# Main.net
KiCad netlist of a schematic drawn in Altium Designer
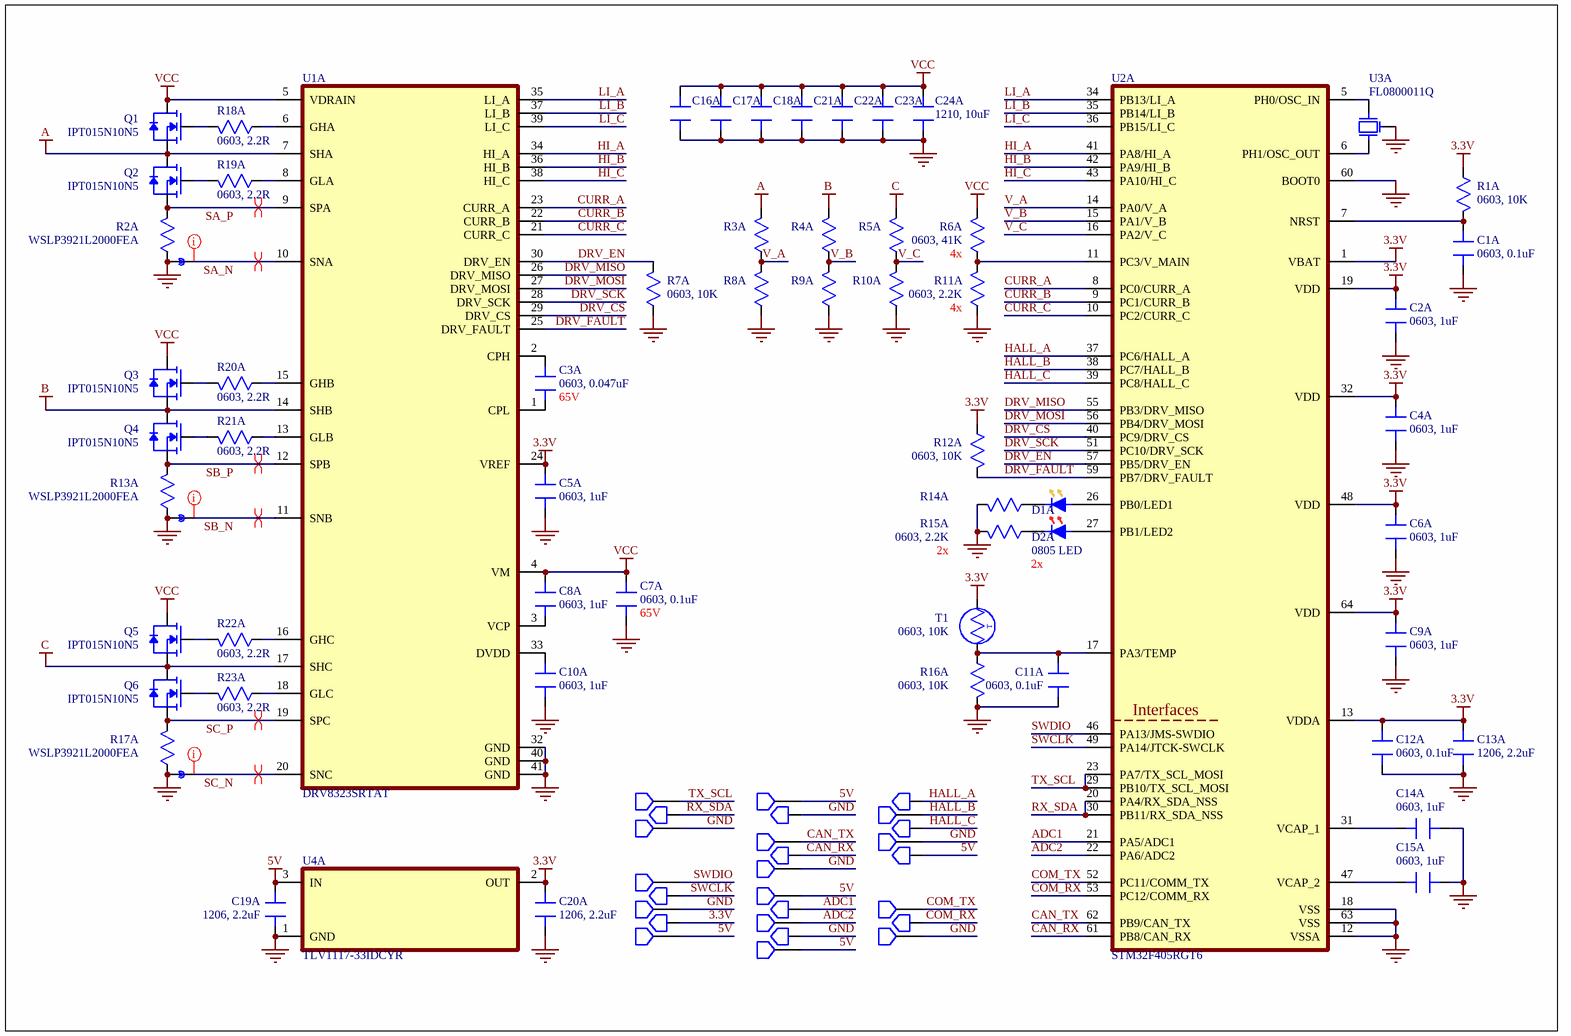
[diagram p0: Main.SchDoc]

(export (version "E")
  (design (tool "Eeschema 10.0.6"))
  (components
    (comp (ref "*1") (value "NetTie") (footprint "NETTİE") (libsource (lib "Passives") (part "NetTie")))
    (comp (ref "*2") (value "NetTie") (footprint "NETTİE") (libsource (lib "Passives") (part "NetTie")))
    (comp (ref "*3") (value "NetTie") (footprint "NETTİE") (libsource (lib "Passives") (part "NetTie")))
    (comp (ref "C1A")
      (value "0603, 0.1uF")
      (footprint "CAP 0603_1608")
      (libsource (lib "Passives") (part "0603 Kapasitör"))
    )
    (comp (ref "C2A")
      (value "0603, 1uF")
      (footprint "CAP 0603_1608")
      (libsource (lib "Passives") (part "0603 Kapasitör"))
    )
    (comp (ref "C3A")
      (value "0603, 0.047uF")
      (footprint "CAP 0603_1608")
      (libsource (lib "Passives") (part "0603 Kapasitör"))
    )
    (comp (ref "C4A")
      (value "0603, 1uF")
      (footprint "CAP 0603_1608")
      (libsource (lib "Passives") (part "0603 Kapasitör"))
    )
    (comp (ref "C5A")
      (value "0603, 1uF")
      (footprint "CAP 0603_1608")
      (libsource (lib "Passives") (part "0603 Kapasitör"))
    )
    (comp (ref "C6A")
      (value "0603, 1uF")
      (footprint "CAP 0603_1608")
      (libsource (lib "Passives") (part "0603 Kapasitör"))
    )
    (comp (ref "C7A")
      (value "0603, 0.1uF")
      (footprint "CAP 0603_1608")
      (libsource (lib "Passives") (part "0603 Kapasitör"))
    )
    (comp (ref "C8A")
      (value "0603, 1uF")
      (footprint "CAP 0603_1608")
      (libsource (lib "Passives") (part "0603 Kapasitör"))
    )
    (comp (ref "C9A")
      (value "0603, 1uF")
      (footprint "CAP 0603_1608")
      (libsource (lib "Passives") (part "0603 Kapasitör"))
    )
    (comp (ref "C10A")
      (value "0603, 1uF")
      (footprint "CAP 0603_1608")
      (libsource (lib "Passives") (part "0603 Kapasitör"))
    )
    (comp (ref "C11A")
      (value "0603, 0.1uF")
      (footprint "CAP 0603_1608")
      (libsource (lib "Passives") (part "0603 Kapasitör"))
    )
    (comp (ref "C12A")
      (value "0603, 0.1uF")
      (footprint "CAP 0603_1608")
      (libsource (lib "Passives") (part "0603 Kapasitör"))
    )
    (comp (ref "C13A")
      (value "1206, 2.2uF")
      (footprint "CAP 1206_3216")
      (libsource (lib "Passives") (part "1206 Kapasitör"))
    )
    (comp (ref "C14A")
      (value "0603, 1uF")
      (footprint "CAP 0603_1608")
      (libsource (lib "Passives") (part "0603 Kapasitör"))
    )
    (comp (ref "C15A")
      (value "0603, 1uF")
      (footprint "CAP 0603_1608")
      (libsource (lib "Passives") (part "0603 Kapasitör"))
    )
    (comp (ref "C16A")
      (value "1210, 10uF")
      (footprint "CAP 1210_3225 - 2.5MM")
      (libsource (lib "Passives") (part "1210 Kapasitör"))
    )
    (comp (ref "C17A")
      (value "1210, 10uF")
      (footprint "CAP 1210_3225 - 2.5MM")
      (libsource (lib "Passives") (part "1210 Kapasitör"))
    )
    (comp (ref "C18A")
      (value "1210, 10uF")
      (footprint "CAP 1210_3225 - 2.5MM")
      (libsource (lib "Passives") (part "1210 Kapasitör"))
    )
    (comp (ref "C19A")
      (value "1206, 2.2uF")
      (footprint "CAP 1206_3216")
      (libsource (lib "Passives") (part "1206 Kapasitör"))
    )
    (comp (ref "C20A")
      (value "1206, 2.2uF")
      (footprint "CAP 1206_3216")
      (libsource (lib "Passives") (part "1206 Kapasitör"))
    )
    (comp (ref "C21A")
      (value "1210, 10uF")
      (footprint "CAP 1210_3225 - 2.5MM")
      (libsource (lib "Passives") (part "1210 Kapasitör"))
    )
    (comp (ref "C22A")
      (value "1210, 10uF")
      (footprint "CAP 1210_3225 - 2.5MM")
      (libsource (lib "Passives") (part "1210 Kapasitör"))
    )
    (comp (ref "C23A")
      (value "1210, 10uF")
      (footprint "CAP 1210_3225 - 2.5MM")
      (libsource (lib "Passives") (part "1210 Kapasitör"))
    )
    (comp (ref "C24A")
      (value "1210, 10uF")
      (footprint "CAP 1210_3225 - 2.5MM")
      (libsource (lib "Passives") (part "1210 Kapasitör"))
    )
    (comp (ref "D1A")
      (value "0805 LED Yellow")
      (footprint "LED 0805_2012 YELLOW")
      (libsource (lib "Passives") (part "0805 LED Yellow"))
    )
    (comp (ref "D2A")
      (value "0805 LED Red")
      (footprint "LED 0805_2012 RED")
      (libsource (lib "Passives") (part "0805 LED Red"))
    )
    (comp (ref "P1") (value "Pad1") (footprint "PAD") (libsource (lib "Passives") (part "Pad1")))
    (comp (ref "P2") (value "Pad1") (footprint "PAD") (libsource (lib "Passives") (part "Pad1")))
    (comp (ref "P4") (value "Pad0") (footprint "PAD") (libsource (lib "Passives") (part "Pad0")))
    (comp (ref "P5") (value "Pad0") (footprint "PAD") (libsource (lib "Passives") (part "Pad0")))
    (comp (ref "P6") (value "Pad0") (footprint "PAD") (libsource (lib "Passives") (part "Pad0")))
    (comp (ref "P7") (value "Pad1") (footprint "PAD") (libsource (lib "Passives") (part "Pad1")))
    (comp (ref "P8") (value "Pad1") (footprint "PAD") (libsource (lib "Passives") (part "Pad1")))
    (comp (ref "P9") (value "Pad1") (footprint "PAD") (libsource (lib "Passives") (part "Pad1")))
    (comp (ref "P10") (value "Pad0") (footprint "PAD") (libsource (lib "Passives") (part "Pad0")))
    (comp (ref "P11") (value "Pad0") (footprint "PAD") (libsource (lib "Passives") (part "Pad0")))
    (comp (ref "P12") (value "Pad1") (footprint "PAD") (libsource (lib "Passives") (part "Pad1")))
    (comp (ref "P13") (value "Pad1") (footprint "PAD") (libsource (lib "Passives") (part "Pad1")))
    (comp (ref "P14") (value "Pad0") (footprint "PAD") (libsource (lib "Passives") (part "Pad0")))
    (comp (ref "P15") (value "Pad1") (footprint "PAD") (libsource (lib "Passives") (part "Pad1")))
    (comp (ref "P16") (value "Pad0") (footprint "PAD") (libsource (lib "Passives") (part "Pad0")))
    (comp (ref "P17") (value "Pad0") (footprint "PAD") (libsource (lib "Passives") (part "Pad0")))
    (comp (ref "P18") (value "Pad1") (footprint "PAD") (libsource (lib "Passives") (part "Pad1")))
    (comp (ref "P19") (value "Pad1") (footprint "PAD") (libsource (lib "Passives") (part "Pad1")))
    (comp (ref "P20") (value "Pad1") (footprint "PAD") (libsource (lib "Passives") (part "Pad1")))
    (comp (ref "P21") (value "Pad0") (footprint "PAD") (libsource (lib "Passives") (part "Pad0")))
    (comp (ref "P22") (value "Pad0") (footprint "PAD") (libsource (lib "Passives") (part "Pad0")))
    (comp (ref "P23") (value "Pad0") (footprint "PAD") (libsource (lib "Passives") (part "Pad0")))
    (comp (ref "P24") (value "Pad1") (footprint "PAD") (libsource (lib "Passives") (part "Pad1")))
    (comp (ref "P25") (value "Pad1") (footprint "PAD") (libsource (lib "Passives") (part "Pad1")))
    (comp (ref "P26") (value "Pad1") (footprint "PAD") (libsource (lib "Passives") (part "Pad1")))
    (comp (ref "P27") (value "Pad1") (footprint "PAD") (libsource (lib "Passives") (part "Pad1")))
    (comp (ref "Q1")
      (value "IPT015N10N5")
      (footprint "IPT015N10N5")
      (libsource (lib "IPT015N10N5") (part "IPT015N10N5"))
    )
    (comp (ref "Q2")
      (value "IPT015N10N5")
      (footprint "IPT015N10N5")
      (libsource (lib "IPT015N10N5") (part "IPT015N10N5"))
    )
    (comp (ref "Q3")
      (value "IPT015N10N5")
      (footprint "IPT015N10N5")
      (libsource (lib "IPT015N10N5") (part "IPT015N10N5"))
    )
    (comp (ref "Q4")
      (value "IPT015N10N5")
      (footprint "IPT015N10N5")
      (libsource (lib "IPT015N10N5") (part "IPT015N10N5"))
    )
    (comp (ref "Q5")
      (value "IPT015N10N5")
      (footprint "IPT015N10N5")
      (libsource (lib "IPT015N10N5") (part "IPT015N10N5"))
    )
    (comp (ref "Q6")
      (value "IPT015N10N5")
      (footprint "IPT015N10N5")
      (libsource (lib "IPT015N10N5") (part "IPT015N10N5"))
    )
    (comp (ref "R1A")
      (value "0603, 10K")
      (footprint "RES 0603_1608")
      (libsource (lib "Passives") (part "0603 Direnç"))
    )
    (comp (ref "R2A")
      (value "WSLP3921L2000FEA")
      (footprint "WSLP3921L2000FEA")
      (libsource (lib "WSLP3921L2000FEA") (part "WSLP3921L2000FEA"))
    )
    (comp (ref "R3A")
      (value "0603, 41K")
      (footprint "RES 0603_1608")
      (libsource (lib "Passives") (part "0603 Direnç"))
    )
    (comp (ref "R4A")
      (value "0603, 41K")
      (footprint "RES 0603_1608")
      (libsource (lib "Passives") (part "0603 Direnç"))
    )
    (comp (ref "R5A")
      (value "0603, 41K")
      (footprint "RES 0603_1608")
      (libsource (lib "Passives") (part "0603 Direnç"))
    )
    (comp (ref "R6A")
      (value "0603, 41K")
      (footprint "RES 0603_1608")
      (libsource (lib "Passives") (part "0603 Direnç"))
    )
    (comp (ref "R7A")
      (value "0603, 10K")
      (footprint "RES 0603_1608")
      (libsource (lib "Passives") (part "0603 Direnç"))
    )
    (comp (ref "R8A")
      (value "0603, 2.2K")
      (footprint "RES 0603_1608")
      (libsource (lib "Passives") (part "0603 Direnç"))
    )
    (comp (ref "R9A")
      (value "0603, 2.2K")
      (footprint "RES 0603_1608")
      (libsource (lib "Passives") (part "0603 Direnç"))
    )
    (comp (ref "R10A")
      (value "0603, 2.2K")
      (footprint "RES 0603_1608")
      (libsource (lib "Passives") (part "0603 Direnç"))
    )
    (comp (ref "R11A")
      (value "0603, 2.2K")
      (footprint "RES 0603_1608")
      (libsource (lib "Passives") (part "0603 Direnç"))
    )
    (comp (ref "R12A")
      (value "0603, 10K")
      (footprint "RES 0603_1608")
      (libsource (lib "Passives") (part "0603 Direnç"))
    )
    (comp (ref "R13A")
      (value "WSLP3921L2000FEA")
      (footprint "WSLP3921L2000FEA")
      (libsource (lib "WSLP3921L2000FEA") (part "WSLP3921L2000FEA"))
    )
    (comp (ref "R14A")
      (value "0603, 2.2K")
      (footprint "RES 0603_1608")
      (libsource (lib "Passives") (part "0603 Direnç"))
    )
    (comp (ref "R15A")
      (value "0603, 2.2K")
      (footprint "RES 0603_1608")
      (libsource (lib "Passives") (part "0603 Direnç"))
    )
    (comp (ref "R16A")
      (value "0603, 10K")
      (footprint "RES 0603_1608")
      (libsource (lib "Passives") (part "0603 Direnç"))
    )
    (comp (ref "R17A")
      (value "WSLP3921L2000FEA")
      (footprint "WSLP3921L2000FEA")
      (libsource (lib "WSLP3921L2000FEA") (part "WSLP3921L2000FEA"))
    )
    (comp (ref "R18A")
      (value "0603, 2.2R")
      (footprint "RES 0603_1608")
      (libsource (lib "Passives") (part "0603 Direnç"))
    )
    (comp (ref "R19A")
      (value "0603, 2.2R")
      (footprint "RES 0603_1608")
      (libsource (lib "Passives") (part "0603 Direnç"))
    )
    (comp (ref "R20A")
      (value "0603, 2.2R")
      (footprint "RES 0603_1608")
      (libsource (lib "Passives") (part "0603 Direnç"))
    )
    (comp (ref "R21A")
      (value "0603, 2.2R")
      (footprint "RES 0603_1608")
      (libsource (lib "Passives") (part "0603 Direnç"))
    )
    (comp (ref "R22A")
      (value "0603, 2.2R")
      (footprint "RES 0603_1608")
      (libsource (lib "Passives") (part "0603 Direnç"))
    )
    (comp (ref "R23A")
      (value "0603, 2.2R")
      (footprint "RES 0603_1608")
      (libsource (lib "Passives") (part "0603 Direnç"))
    )
    (comp (ref "T1")
      (value "0603, 10K")
      (footprint "RES 0603_1608")
      (libsource (lib "Passives") (part "0603 Direnç"))
    )
    (comp (ref "U1A")
      (value "DRV8323SRTAT")
      (footprint "DRV8323SRTAT")
      (libsource (lib "DRV8323SRTAT") (part "DRV8323SRTAT"))
    )
    (comp (ref "U2A")
      (value "STM32F405RGT6")
      (footprint "STM32F405RGT6")
      (libsource (lib "STM32F405RGT6") (part "STM32F405RGT6"))
    )
    (comp (ref "U3A")
      (value "FL0800011Q")
      (footprint "FL0800011Q")
      (libsource (lib "FL0800011Q") (part "FL0800011Q"))
    )
    (comp (ref "U4A")
      (value "TLV1117-33IDCYR")
      (footprint "TLV1117-33IDCYR")
      (libsource (lib "TLV1117-33IDCYR") (part "TLV1117-33IDCYR"))
    )
  )
  (nets
    (net (code "1") (name "/ADC1") (class "Default")
      (node (ref "P17") (pin "1") (pinfunction "1_1") (pintype "passive"))
      (node (ref "U2A") (pin "21") (pinfunction "PA5/ADC1_21") (pintype "passive"))
    )
    (net (code "2") (name "/ADC2") (class "Default")
      (node (ref "P19") (pin "1") (pinfunction "1_1") (pintype "passive"))
      (node (ref "U2A") (pin "22") (pinfunction "PA6/ADC2_22") (pintype "passive"))
    )
    (net (code "3") (name "/CAN_RX") (class "Default")
      (node (ref "P11") (pin "1") (pinfunction "1_1") (pintype "passive"))
      (node (ref "U2A") (pin "61") (pinfunction "PB8/CAN_RX_61") (pintype "passive"))
    )
    (net (code "4") (name "/CAN_TX") (class "Default")
      (node (ref "P9") (pin "1") (pinfunction "1_1") (pintype "passive"))
      (node (ref "U2A") (pin "62") (pinfunction "PB9/CAN_TX_62") (pintype "passive"))
    )
    (net (code "5") (name "/COM_RX") (class "Default")
      (node (ref "P23") (pin "1") (pinfunction "1_1") (pintype "passive"))
      (node (ref "U2A") (pin "53") (pinfunction "PC12/COMM_RX_53") (pintype "passive"))
    )
    (net (code "6") (name "/COM_TX") (class "Default")
      (node (ref "P20") (pin "1") (pinfunction "1_1") (pintype "passive"))
      (node (ref "U2A") (pin "52") (pinfunction "PC11/COMM_TX_52") (pintype "passive"))
    )
    (net (code "7") (name "/CURR_A") (class "Default")
      (node (ref "U1A") (pin "23") (pinfunction "CURR_A_23") (pintype "passive"))
      (node (ref "U2A") (pin "8") (pinfunction "PC0/CURR_A_8") (pintype "passive"))
    )
    (net (code "8") (name "/CURR_B") (class "Default")
      (node (ref "U1A") (pin "22") (pinfunction "CURR_B_22") (pintype "passive"))
      (node (ref "U2A") (pin "9") (pinfunction "PC1/CURR_B_9") (pintype "passive"))
    )
    (net (code "9") (name "/CURR_C") (class "Default")
      (node (ref "U1A") (pin "21") (pinfunction "CURR_C_21") (pintype "passive"))
      (node (ref "U2A") (pin "10") (pinfunction "PC2/CURR_C_10") (pintype "passive"))
    )
    (net (code "10") (name "/DRV_CS") (class "Default")
      (node (ref "U1A") (pin "29") (pinfunction "DRV_CS_29") (pintype "passive"))
      (node (ref "U2A") (pin "40") (pinfunction "PC9/DRV_CS_40") (pintype "passive"))
    )
    (net (code "11") (name "/DRV_EN") (class "Default")
      (node (ref "R7A") (pin "2") (pinfunction "2_2") (pintype "passive"))
      (node (ref "U1A") (pin "30") (pinfunction "DRV_EN_30") (pintype "passive"))
      (node (ref "U2A") (pin "57") (pinfunction "PB5/DRV_EN_57") (pintype "passive"))
    )
    (net (code "12") (name "/DRV_FAULT") (class "Default")
      (node (ref "R12A") (pin "1") (pinfunction "1_1") (pintype "passive"))
      (node (ref "U1A") (pin "25") (pinfunction "DRV_FAULT_25") (pintype "passive"))
      (node (ref "U2A") (pin "59") (pinfunction "PB7/DRV_FAULT_59") (pintype "passive"))
    )
    (net (code "13") (name "/DRV_MISO") (class "Default")
      (node (ref "U1A") (pin "26") (pinfunction "DRV_MISO_26") (pintype "passive"))
      (node (ref "U2A") (pin "55") (pinfunction "PB3/DRV_MISO_55") (pintype "passive"))
    )
    (net (code "14") (name "/DRV_MOSI") (class "Default")
      (node (ref "U1A") (pin "27") (pinfunction "DRV_MOSI_27") (pintype "passive"))
      (node (ref "U2A") (pin "56") (pinfunction "PB4/DRV_MOSI_56") (pintype "passive"))
    )
    (net (code "15") (name "/DRV_SCK") (class "Default")
      (node (ref "U1A") (pin "28") (pinfunction "DRV_SCK_28") (pintype "passive"))
      (node (ref "U2A") (pin "51") (pinfunction "PC10/DRV_SCK_51") (pintype "passive"))
    )
    (net (code "16") (name "/HALL_A") (class "Default")
      (node (ref "P6") (pin "1") (pinfunction "1_1") (pintype "passive"))
      (node (ref "U2A") (pin "37") (pinfunction "PC6/HALL_A_37") (pintype "passive"))
    )
    (net (code "17") (name "/HALL_B") (class "Default")
      (node (ref "P8") (pin "1") (pinfunction "1_1") (pintype "passive"))
      (node (ref "U2A") (pin "38") (pinfunction "PC7/HALL_B_38") (pintype "passive"))
    )
    (net (code "18") (name "/HALL_C") (class "Default")
      (node (ref "P10") (pin "1") (pinfunction "1_1") (pintype "passive"))
      (node (ref "U2A") (pin "39") (pinfunction "PC8/HALL_C_39") (pintype "passive"))
    )
    (net (code "19") (name "/HI_A") (class "Default")
      (node (ref "U1A") (pin "34") (pinfunction "HI_A_34") (pintype "passive"))
      (node (ref "U2A") (pin "41") (pinfunction "PA8/HI_A_41") (pintype "passive"))
    )
    (net (code "20") (name "/HI_B") (class "Default")
      (node (ref "U1A") (pin "36") (pinfunction "HI_B_36") (pintype "passive"))
      (node (ref "U2A") (pin "42") (pinfunction "PA9/HI_B_42") (pintype "passive"))
    )
    (net (code "21") (name "/HI_C") (class "Default")
      (node (ref "U1A") (pin "38") (pinfunction "HI_C_38") (pintype "passive"))
      (node (ref "U2A") (pin "43") (pinfunction "PA10/HI_C_43") (pintype "passive"))
    )
    (net (code "22") (name "/LI_A") (class "Default")
      (node (ref "U1A") (pin "35") (pinfunction "LI_A_35") (pintype "passive"))
      (node (ref "U2A") (pin "34") (pinfunction "PB13/LI_A_34") (pintype "passive"))
    )
    (net (code "23") (name "/LI_B") (class "Default")
      (node (ref "U1A") (pin "37") (pinfunction "LI_B_37") (pintype "passive"))
      (node (ref "U2A") (pin "35") (pinfunction "PB14/LI_B_35") (pintype "passive"))
    )
    (net (code "24") (name "/LI_C") (class "Default")
      (node (ref "U1A") (pin "39") (pinfunction "LI_C_39") (pintype "passive"))
      (node (ref "U2A") (pin "36") (pinfunction "PB15/LI_C_36") (pintype "passive"))
    )
    (net (code "25") (name "/RX_SDA") (class "Default")
      (node (ref "P4") (pin "1") (pinfunction "1_1") (pintype "passive"))
      (node (ref "U2A") (pin "20") (pinfunction "PA4/RX_SDA_NSS_20") (pintype "passive"))
      (node (ref "U2A") (pin "30") (pinfunction "PB11/RX_SDA_NSS_30") (pintype "passive"))
    )
    (net (code "26") (name "/SA_N") (class "Default")
      (node (ref "*1") (pin "1") (pinfunction "1_1") (pintype "passive"))
      (node (ref "U1A") (pin "10") (pinfunction "SNA_10") (pintype "passive"))
    )
    (net (code "27") (name "/SA_P") (class "Default")
      (node (ref "Q2") (pin "S1") (pinfunction "S_S1") (pintype "passive"))
      (node (ref "R2A") (pin "2") (pinfunction "2_2") (pintype "passive"))
      (node (ref "U1A") (pin "9") (pinfunction "SPA_9") (pintype "passive"))
    )
    (net (code "28") (name "/SB_N") (class "Default")
      (node (ref "*2") (pin "1") (pinfunction "1_1") (pintype "passive"))
      (node (ref "U1A") (pin "11") (pinfunction "SNB_11") (pintype "passive"))
    )
    (net (code "29") (name "/SB_P") (class "Default")
      (node (ref "Q4") (pin "S1") (pinfunction "S_S1") (pintype "passive"))
      (node (ref "R13A") (pin "2") (pinfunction "2_2") (pintype "passive"))
      (node (ref "U1A") (pin "12") (pinfunction "SPB_12") (pintype "passive"))
    )
    (net (code "30") (name "/SC_N") (class "Default")
      (node (ref "*3") (pin "1") (pinfunction "1_1") (pintype "passive"))
      (node (ref "U1A") (pin "20") (pinfunction "SNC_20") (pintype "passive"))
    )
    (net (code "31") (name "/SC_P") (class "Default")
      (node (ref "Q6") (pin "S1") (pinfunction "S_S1") (pintype "passive"))
      (node (ref "R17A") (pin "2") (pinfunction "2_2") (pintype "passive"))
      (node (ref "U1A") (pin "19") (pinfunction "SPC_19") (pintype "passive"))
    )
    (net (code "32") (name "/SWCLK") (class "Default")
      (node (ref "P16") (pin "1") (pinfunction "1_1") (pintype "passive"))
      (node (ref "U2A") (pin "49") (pinfunction "PA14/JTCK-SWCLK_49") (pintype "passive"))
    )
    (net (code "33") (name "/SWDIO") (class "Default")
      (node (ref "P15") (pin "1") (pinfunction "1_1") (pintype "passive"))
      (node (ref "U2A") (pin "46") (pinfunction "PA13/JMS-SWDIO_46") (pintype "passive"))
    )
    (net (code "34") (name "/TX_SCL") (class "Default")
      (node (ref "P1") (pin "1") (pinfunction "1_1") (pintype "passive"))
      (node (ref "U2A") (pin "23") (pinfunction "PA7/TX_SCL_MOSI_23") (pintype "passive"))
      (node (ref "U2A") (pin "29") (pinfunction "PB10/TX_SCL_MOSI_29") (pintype "passive"))
    )
    (net (code "35") (name "/V_A") (class "Default")
      (node (ref "R3A") (pin "1") (pinfunction "1_1") (pintype "passive"))
      (node (ref "R8A") (pin "2") (pinfunction "2_2") (pintype "passive"))
      (node (ref "U2A") (pin "14") (pinfunction "PA0/V_A_14") (pintype "passive"))
    )
    (net (code "36") (name "/V_B") (class "Default")
      (node (ref "R4A") (pin "1") (pinfunction "1_1") (pintype "passive"))
      (node (ref "R9A") (pin "2") (pinfunction "2_2") (pintype "passive"))
      (node (ref "U2A") (pin "15") (pinfunction "PA1/V_B_15") (pintype "passive"))
    )
    (net (code "37") (name "/V_C") (class "Default")
      (node (ref "R10A") (pin "2") (pinfunction "2_2") (pintype "passive"))
      (node (ref "R5A") (pin "1") (pinfunction "1_1") (pintype "passive"))
      (node (ref "U2A") (pin "16") (pinfunction "PA2/V_C_16") (pintype "passive"))
    )
    (net (code "38") (name "3.3V") (class "Default")
      (node (ref "C12A") (pin "1") (pinfunction "1_1") (pintype "passive"))
      (node (ref "C13A") (pin "2") (pinfunction "2_2") (pintype "passive"))
      (node (ref "C20A") (pin "2") (pinfunction "2_2") (pintype "passive"))
      (node (ref "C2A") (pin "1") (pinfunction "1_1") (pintype "passive"))
      (node (ref "C4A") (pin "1") (pinfunction "1_1") (pintype "passive"))
      (node (ref "C5A") (pin "1") (pinfunction "1_1") (pintype "passive"))
      (node (ref "C6A") (pin "1") (pinfunction "1_1") (pintype "passive"))
      (node (ref "C9A") (pin "1") (pinfunction "1_1") (pintype "passive"))
      (node (ref "P21") (pin "1") (pinfunction "1_1") (pintype "passive"))
      (node (ref "R12A") (pin "2") (pinfunction "2_2") (pintype "passive"))
      (node (ref "R1A") (pin "2") (pinfunction "2_2") (pintype "passive"))
      (node (ref "T1") (pin "2") (pinfunction "2_2") (pintype "passive"))
      (node (ref "U1A") (pin "24") (pinfunction "VREF_24") (pintype "passive"))
      (node (ref "U2A") (pin "1") (pinfunction "VBAT_1") (pintype "passive"))
      (node (ref "U2A") (pin "13") (pinfunction "VDDA_13") (pintype "passive"))
      (node (ref "U2A") (pin "19") (pinfunction "VDD_19") (pintype "passive"))
      (node (ref "U2A") (pin "32") (pinfunction "VDD_32") (pintype "passive"))
      (node (ref "U2A") (pin "48") (pinfunction "VDD_48") (pintype "passive"))
      (node (ref "U2A") (pin "64") (pinfunction "VDD_64") (pintype "passive"))
      (node (ref "U4A") (pin "2") (pinfunction "OUT_2") (pintype "passive"))
    )
    (net (code "39") (name "5V") (class "Default")
      (node (ref "C19A") (pin "2") (pinfunction "2_2") (pintype "passive"))
      (node (ref "P14") (pin "1") (pinfunction "1_1") (pintype "passive"))
      (node (ref "P2") (pin "1") (pinfunction "1_1") (pintype "passive"))
      (node (ref "P24") (pin "1") (pinfunction "1_1") (pintype "passive"))
      (node (ref "P25") (pin "1") (pinfunction "1_1") (pintype "passive"))
      (node (ref "P27") (pin "1") (pinfunction "1_1") (pintype "passive"))
      (node (ref "U4A") (pin "3") (pinfunction "IN_3") (pintype "passive"))
    )
    (net (code "40") (name "A") (class "Default")
      (node (ref "Q1") (pin "S1") (pinfunction "S_S1") (pintype "passive"))
      (node (ref "Q2") (pin "TAP") (pinfunction "D_TAP") (pintype "passive"))
      (node (ref "R3A") (pin "2") (pinfunction "2_2") (pintype "passive"))
      (node (ref "U1A") (pin "7") (pinfunction "SHA_7") (pintype "passive"))
    )
    (net (code "41") (name "B") (class "Default")
      (node (ref "Q3") (pin "S1") (pinfunction "S_S1") (pintype "passive"))
      (node (ref "Q4") (pin "TAP") (pinfunction "D_TAP") (pintype "passive"))
      (node (ref "R4A") (pin "2") (pinfunction "2_2") (pintype "passive"))
      (node (ref "U1A") (pin "14") (pinfunction "SHB_14") (pintype "passive"))
    )
    (net (code "42") (name "C") (class "Default")
      (node (ref "Q5") (pin "S1") (pinfunction "S_S1") (pintype "passive"))
      (node (ref "Q6") (pin "TAP") (pinfunction "D_TAP") (pintype "passive"))
      (node (ref "R5A") (pin "2") (pinfunction "2_2") (pintype "passive"))
      (node (ref "U1A") (pin "17") (pinfunction "SHC_17") (pintype "passive"))
    )
    (net (code "43") (name "GND") (class "Default")
      (node (ref "*1") (pin "0") (pinfunction "0_0") (pintype "passive"))
      (node (ref "*2") (pin "0") (pinfunction "0_0") (pintype "passive"))
      (node (ref "*3") (pin "0") (pinfunction "0_0") (pintype "passive"))
      (node (ref "C10A") (pin "2") (pinfunction "2_2") (pintype "passive"))
      (node (ref "C11A") (pin "2") (pinfunction "2_2") (pintype "passive"))
      (node (ref "C12A") (pin "2") (pinfunction "2_2") (pintype "passive"))
      (node (ref "C13A") (pin "1") (pinfunction "1_1") (pintype "passive"))
      (node (ref "C14A") (pin "1") (pinfunction "1_1") (pintype "passive"))
      (node (ref "C15A") (pin "1") (pinfunction "1_1") (pintype "passive"))
      (node (ref "C16A") (pin "1") (pinfunction "1_1") (pintype "passive"))
      (node (ref "C17A") (pin "1") (pinfunction "1_1") (pintype "passive"))
      (node (ref "C18A") (pin "1") (pinfunction "1_1") (pintype "passive"))
      (node (ref "C19A") (pin "1") (pinfunction "1_1") (pintype "passive"))
      (node (ref "C1A") (pin "2") (pinfunction "2_2") (pintype "passive"))
      (node (ref "C20A") (pin "1") (pinfunction "1_1") (pintype "passive"))
      (node (ref "C21A") (pin "1") (pinfunction "1_1") (pintype "passive"))
      (node (ref "C22A") (pin "1") (pinfunction "1_1") (pintype "passive"))
      (node (ref "C23A") (pin "1") (pinfunction "1_1") (pintype "passive"))
      (node (ref "C24A") (pin "1") (pinfunction "1_1") (pintype "passive"))
      (node (ref "C2A") (pin "2") (pinfunction "2_2") (pintype "passive"))
      (node (ref "C4A") (pin "2") (pinfunction "2_2") (pintype "passive"))
      (node (ref "C5A") (pin "2") (pinfunction "2_2") (pintype "passive"))
      (node (ref "C6A") (pin "2") (pinfunction "2_2") (pintype "passive"))
      (node (ref "C7A") (pin "2") (pinfunction "2_2") (pintype "passive"))
      (node (ref "C9A") (pin "2") (pinfunction "2_2") (pintype "passive"))
      (node (ref "P12") (pin "1") (pinfunction "1_1") (pintype "passive"))
      (node (ref "P13") (pin "1") (pinfunction "1_1") (pintype "passive"))
      (node (ref "P18") (pin "1") (pinfunction "1_1") (pintype "passive"))
      (node (ref "P22") (pin "1") (pinfunction "1_1") (pintype "passive"))
      (node (ref "P26") (pin "1") (pinfunction "1_1") (pintype "passive"))
      (node (ref "P5") (pin "1") (pinfunction "1_1") (pintype "passive"))
      (node (ref "P7") (pin "1") (pinfunction "1_1") (pintype "passive"))
      (node (ref "R10A") (pin "1") (pinfunction "1_1") (pintype "passive"))
      (node (ref "R11A") (pin "1") (pinfunction "1_1") (pintype "passive"))
      (node (ref "R13A") (pin "1") (pinfunction "1_1") (pintype "passive"))
      (node (ref "R14A") (pin "2") (pinfunction "2_2") (pintype "passive"))
      (node (ref "R15A") (pin "2") (pinfunction "2_2") (pintype "passive"))
      (node (ref "R16A") (pin "1") (pinfunction "1_1") (pintype "passive"))
      (node (ref "R17A") (pin "1") (pinfunction "1_1") (pintype "passive"))
      (node (ref "R2A") (pin "1") (pinfunction "1_1") (pintype "passive"))
      (node (ref "R7A") (pin "1") (pinfunction "1_1") (pintype "passive"))
      (node (ref "R8A") (pin "1") (pinfunction "1_1") (pintype "passive"))
      (node (ref "R9A") (pin "1") (pinfunction "1_1") (pintype "passive"))
      (node (ref "U1A") (pin "32") (pinfunction "GND_32") (pintype "passive"))
      (node (ref "U1A") (pin "40") (pinfunction "GND_40") (pintype "passive"))
      (node (ref "U1A") (pin "41") (pinfunction "GND_41") (pintype "passive"))
      (node (ref "U2A") (pin "12") (pinfunction "VSSA_12") (pintype "passive"))
      (node (ref "U2A") (pin "18") (pinfunction "VSS_18") (pintype "passive"))
      (node (ref "U2A") (pin "60") (pinfunction "BOOT0_60") (pintype "passive"))
      (node (ref "U2A") (pin "63") (pinfunction "VSS_63") (pintype "passive"))
      (node (ref "U3A") (pin "4") (pinfunction "GND_4") (pintype "passive"))
      (node (ref "U4A") (pin "1") (pinfunction "GND_1") (pintype "passive"))
    )
    (net (code "44") (name "Net-(D1A-Pad2)") (class "Default")
      (node (ref "D1A") (pin "2") (pinfunction "2_2") (pintype "passive"))
      (node (ref "R14A") (pin "1") (pinfunction "1_1") (pintype "passive"))
    )
    (net (code "45") (name "Net-(D2A-Pad2)") (class "Default")
      (node (ref "D2A") (pin "2") (pinfunction "2_2") (pintype "passive"))
      (node (ref "R15A") (pin "1") (pinfunction "1_1") (pintype "passive"))
    )
    (net (code "46") (name "Net-(Q1-PadG)") (class "Default")
      (node (ref "Q1") (pin "G") (pinfunction "G_G") (pintype "passive"))
      (node (ref "R18A") (pin "2") (pinfunction "2_2") (pintype "passive"))
    )
    (net (code "47") (name "Net-(Q2-PadG)") (class "Default")
      (node (ref "Q2") (pin "G") (pinfunction "G_G") (pintype "passive"))
      (node (ref "R19A") (pin "2") (pinfunction "2_2") (pintype "passive"))
    )
    (net (code "48") (name "Net-(Q3-PadG)") (class "Default")
      (node (ref "Q3") (pin "G") (pinfunction "G_G") (pintype "passive"))
      (node (ref "R20A") (pin "2") (pinfunction "2_2") (pintype "passive"))
    )
    (net (code "49") (name "Net-(Q4-PadG)") (class "Default")
      (node (ref "Q4") (pin "G") (pinfunction "G_G") (pintype "passive"))
      (node (ref "R21A") (pin "2") (pinfunction "2_2") (pintype "passive"))
    )
    (net (code "50") (name "Net-(Q5-PadG)") (class "Default")
      (node (ref "Q5") (pin "G") (pinfunction "G_G") (pintype "passive"))
      (node (ref "R22A") (pin "2") (pinfunction "2_2") (pintype "passive"))
    )
    (net (code "51") (name "Net-(Q6-PadG)") (class "Default")
      (node (ref "Q6") (pin "G") (pinfunction "G_G") (pintype "passive"))
      (node (ref "R23A") (pin "2") (pinfunction "2_2") (pintype "passive"))
    )
    (net (code "52") (name "Net-(U1A-CPH)") (class "Default")
      (node (ref "C3A") (pin "1") (pinfunction "1_1") (pintype "passive"))
      (node (ref "U1A") (pin "2") (pinfunction "CPH_2") (pintype "passive"))
    )
    (net (code "53") (name "Net-(U1A-CPL)") (class "Default")
      (node (ref "C3A") (pin "2") (pinfunction "2_2") (pintype "passive"))
      (node (ref "U1A") (pin "1") (pinfunction "CPL_1") (pintype "passive"))
    )
    (net (code "54") (name "Net-(U1A-DVDD)") (class "Default")
      (node (ref "C10A") (pin "1") (pinfunction "1_1") (pintype "passive"))
      (node (ref "U1A") (pin "33") (pinfunction "DVDD_33") (pintype "passive"))
    )
    (net (code "55") (name "Net-(U1A-GHA)") (class "Default")
      (node (ref "R18A") (pin "1") (pinfunction "1_1") (pintype "passive"))
      (node (ref "U1A") (pin "6") (pinfunction "GHA_6") (pintype "passive"))
    )
    (net (code "56") (name "Net-(U1A-GHB)") (class "Default")
      (node (ref "R20A") (pin "1") (pinfunction "1_1") (pintype "passive"))
      (node (ref "U1A") (pin "15") (pinfunction "GHB_15") (pintype "passive"))
    )
    (net (code "57") (name "Net-(U1A-GHC)") (class "Default")
      (node (ref "R22A") (pin "1") (pinfunction "1_1") (pintype "passive"))
      (node (ref "U1A") (pin "16") (pinfunction "GHC_16") (pintype "passive"))
    )
    (net (code "58") (name "Net-(U1A-GLA)") (class "Default")
      (node (ref "R19A") (pin "1") (pinfunction "1_1") (pintype "passive"))
      (node (ref "U1A") (pin "8") (pinfunction "GLA_8") (pintype "passive"))
    )
    (net (code "59") (name "Net-(U1A-GLB)") (class "Default")
      (node (ref "R21A") (pin "1") (pinfunction "1_1") (pintype "passive"))
      (node (ref "U1A") (pin "13") (pinfunction "GLB_13") (pintype "passive"))
    )
    (net (code "60") (name "Net-(U1A-GLC)") (class "Default")
      (node (ref "R23A") (pin "1") (pinfunction "1_1") (pintype "passive"))
      (node (ref "U1A") (pin "18") (pinfunction "GLC_18") (pintype "passive"))
    )
    (net (code "61") (name "Net-(U1A-VCP)") (class "Default")
      (node (ref "C8A") (pin "2") (pinfunction "2_2") (pintype "passive"))
      (node (ref "U1A") (pin "3") (pinfunction "VCP_3") (pintype "passive"))
    )
    (net (code "62") (name "Net-(U2A-NRST)") (class "Default")
      (node (ref "C1A") (pin "1") (pinfunction "1_1") (pintype "passive"))
      (node (ref "R1A") (pin "1") (pinfunction "1_1") (pintype "passive"))
      (node (ref "U2A") (pin "7") (pinfunction "NRST_7") (pintype "passive"))
    )
    (net (code "63") (name "Net-(U2A-PA3{slash}TEMP)") (class "Default")
      (node (ref "C11A") (pin "1") (pinfunction "1_1") (pintype "passive"))
      (node (ref "R16A") (pin "2") (pinfunction "2_2") (pintype "passive"))
      (node (ref "T1") (pin "1") (pinfunction "1_1") (pintype "passive"))
      (node (ref "U2A") (pin "17") (pinfunction "PA3/TEMP_17") (pintype "passive"))
    )
    (net (code "64") (name "Net-(U2A-PB0{slash}LED1)") (class "Default")
      (node (ref "D1A") (pin "1") (pinfunction "1_1") (pintype "passive"))
      (node (ref "U2A") (pin "26") (pinfunction "PB0/LED1_26") (pintype "passive"))
    )
    (net (code "65") (name "Net-(U2A-PB1{slash}LED2)") (class "Default")
      (node (ref "D2A") (pin "1") (pinfunction "1_1") (pintype "passive"))
      (node (ref "U2A") (pin "27") (pinfunction "PB1/LED2_27") (pintype "passive"))
    )
    (net (code "66") (name "Net-(U2A-PC3{slash}V_MAIN)") (class "Default")
      (node (ref "R11A") (pin "2") (pinfunction "2_2") (pintype "passive"))
      (node (ref "R6A") (pin "1") (pinfunction "1_1") (pintype "passive"))
      (node (ref "U2A") (pin "11") (pinfunction "PC3/V_MAIN_11") (pintype "passive"))
    )
    (net (code "67") (name "Net-(U2A-PH0{slash}OSC_IN)") (class "Default")
      (node (ref "U2A") (pin "5") (pinfunction "PH0/OSC_IN_5") (pintype "passive"))
      (node (ref "U3A") (pin "3") (pinfunction "2_3") (pintype "passive"))
    )
    (net (code "68") (name "Net-(U2A-PH1{slash}OSC_OUT)") (class "Default")
      (node (ref "U2A") (pin "6") (pinfunction "PH1/OSC_OUT_6") (pintype "passive"))
      (node (ref "U3A") (pin "1") (pinfunction "1_1") (pintype "passive"))
    )
    (net (code "69") (name "Net-(U2A-VCAP_1)") (class "Default")
      (node (ref "C14A") (pin "2") (pinfunction "2_2") (pintype "passive"))
      (node (ref "U2A") (pin "31") (pinfunction "VCAP_1_31") (pintype "passive"))
    )
    (net (code "70") (name "Net-(U2A-VCAP_2)") (class "Default")
      (node (ref "C15A") (pin "2") (pinfunction "2_2") (pintype "passive"))
      (node (ref "U2A") (pin "47") (pinfunction "VCAP_2_47") (pintype "passive"))
    )
    (net (code "71") (name "VCC") (class "Default")
      (node (ref "C16A") (pin "2") (pinfunction "2_2") (pintype "passive"))
      (node (ref "C17A") (pin "2") (pinfunction "2_2") (pintype "passive"))
      (node (ref "C18A") (pin "2") (pinfunction "2_2") (pintype "passive"))
      (node (ref "C21A") (pin "2") (pinfunction "2_2") (pintype "passive"))
      (node (ref "C22A") (pin "2") (pinfunction "2_2") (pintype "passive"))
      (node (ref "C23A") (pin "2") (pinfunction "2_2") (pintype "passive"))
      (node (ref "C24A") (pin "2") (pinfunction "2_2") (pintype "passive"))
      (node (ref "C7A") (pin "1") (pinfunction "1_1") (pintype "passive"))
      (node (ref "C8A") (pin "1") (pinfunction "1_1") (pintype "passive"))
      (node (ref "Q1") (pin "TAP") (pinfunction "D_TAP") (pintype "passive"))
      (node (ref "Q3") (pin "TAP") (pinfunction "D_TAP") (pintype "passive"))
      (node (ref "Q5") (pin "TAP") (pinfunction "D_TAP") (pintype "passive"))
      (node (ref "R6A") (pin "2") (pinfunction "2_2") (pintype "passive"))
      (node (ref "U1A") (pin "4") (pinfunction "VM_4") (pintype "passive"))
      (node (ref "U1A") (pin "5") (pinfunction "VDRAIN_5") (pintype "passive"))
    )
  )
)
